# baseboard.net
KiCad netlist of a schematic drawn in Altium Designer
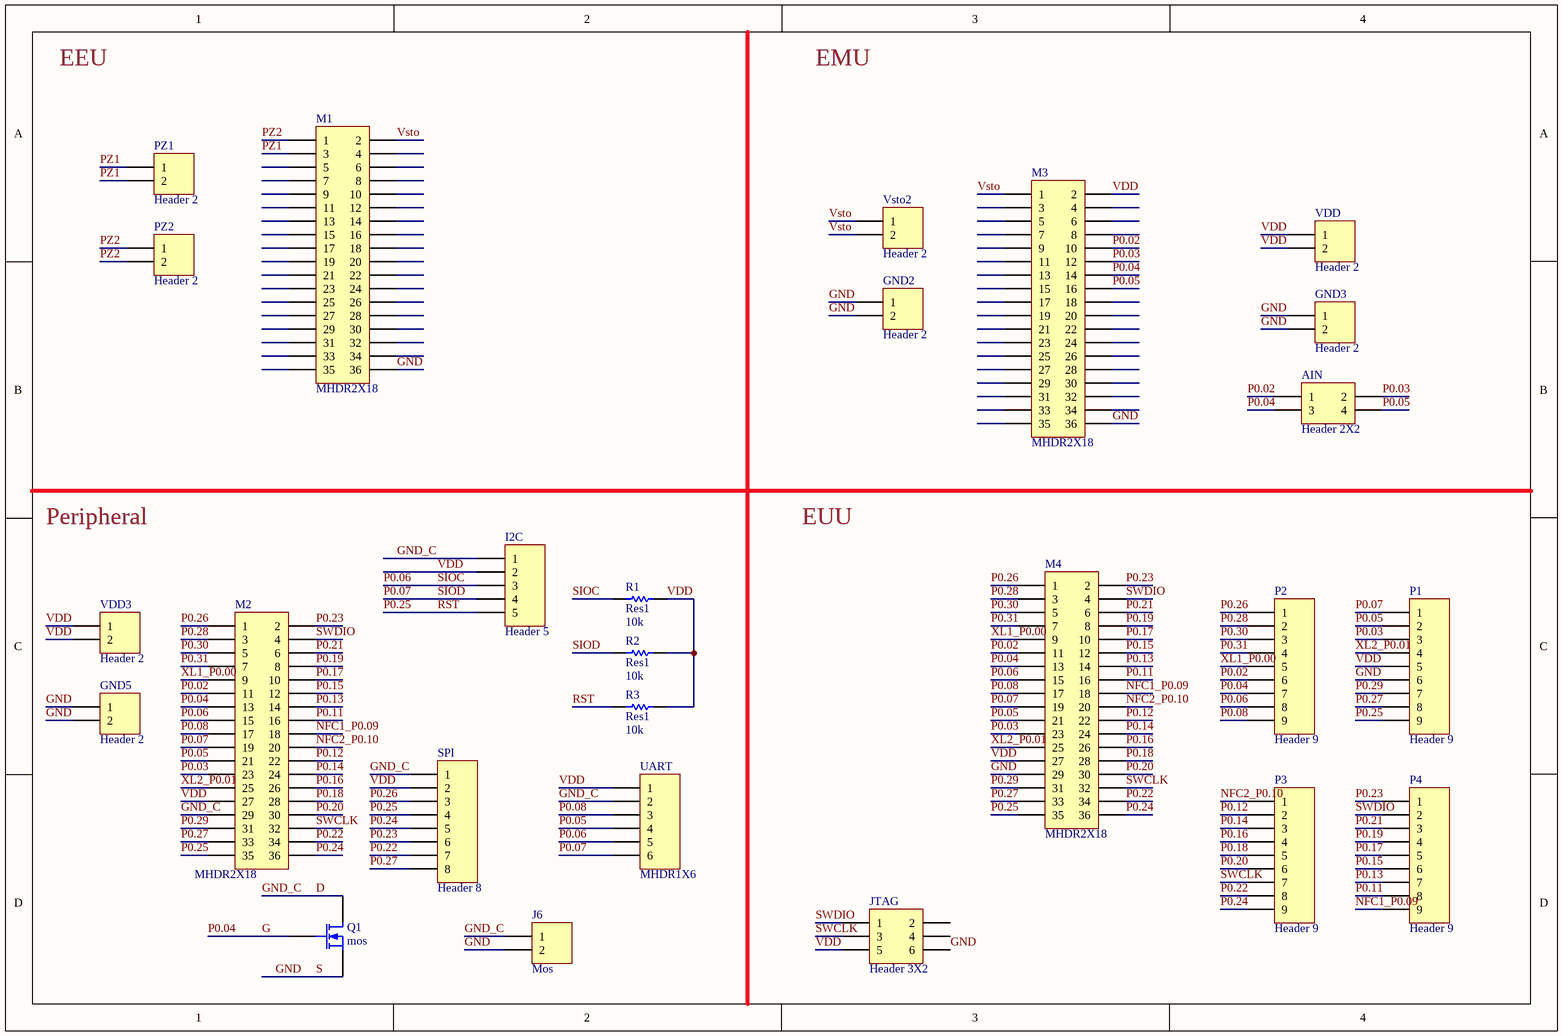
[diagram p0: baseboard.SchDoc]

(export (version "E")
  (design (tool "Eeschema 10.0.6"))
  (components
    (comp (ref "AIN")
      (value "Header 2X2")
      (footprint "HDR2X2")
      (description "Header, 2-Pin, Dual row")
      (fields (field (name "PUBLISHER") "Altium Limited"))
      (libsource (lib "Miscellaneous Connectors") (part "Header 2X2"))
    )
    (comp (ref "GND2")
      (value "Header 2")
      (footprint "HDR1X2")
      (description "Header, 2-Pin")
      (fields (field (name "PUBLISHER") "Altium Limited"))
      (libsource (lib "Miscellaneous Connectors") (part "Header 2"))
    )
    (comp (ref "GND3")
      (value "Header 2")
      (footprint "HDR1X2")
      (description "Header, 2-Pin")
      (fields (field (name "PUBLISHER") "Altium Limited"))
      (libsource (lib "Miscellaneous Connectors") (part "Header 2"))
    )
    (comp (ref "GND5")
      (value "Header 2")
      (footprint "HDR1X2")
      (description "Header, 2-Pin")
      (fields (field (name "PUBLISHER") "Altium Limited"))
      (libsource (lib "Miscellaneous Connectors") (part "Header 2"))
    )
    (comp (ref "I2C")
      (value "Header 5")
      (footprint "HDR1X5")
      (description "Header, 5-Pin")
      (fields (field (name "PUBLISHER") "Altium Limited"))
      (libsource (lib "Miscellaneous Connectors") (part "Header 5"))
    )
    (comp (ref "J6")
      (value "Mos")
      (footprint "HDR1X2")
      (description "Header, 2-Pin")
      (fields (field (name "PUBLISHER") "Altium Limited"))
      (libsource (lib "Miscellaneous Connectors") (part "Header 2"))
    )
    (comp (ref "JTAG")
      (value "Header 3X2")
      (footprint "HDR2X3")
      (description "Header, 3-Pin, Dual row")
      (fields (field (name "PUBLISHER") "Altium Limited"))
      (libsource (lib "Miscellaneous Connectors") (part "Header 3X2"))
    )
    (comp (ref "M1")
      (value "MHDR2X18")
      (footprint "module9x4")
      (description "Header, 18-Pin, Dual row")
      (fields (field (name "PUBLISHER") "Altium Limited"))
      (libsource (lib "Miscellaneous Connectors") (part "MHDR2X18"))
    )
    (comp (ref "M2")
      (value "MHDR2X18")
      (footprint "module9x4")
      (description "Header, 18-Pin, Dual row")
      (fields (field (name "PUBLISHER") "Altium Limited"))
      (libsource (lib "Miscellaneous Connectors") (part "MHDR2X18"))
    )
    (comp (ref "M3")
      (value "MHDR2X18")
      (footprint "module9x4")
      (description "Header, 18-Pin, Dual row")
      (fields (field (name "PUBLISHER") "Altium Limited"))
      (libsource (lib "Miscellaneous Connectors") (part "MHDR2X18"))
    )
    (comp (ref "M4")
      (value "MHDR2X18")
      (footprint "module9x4")
      (description "Header, 18-Pin, Dual row")
      (fields (field (name "PUBLISHER") "Altium Limited"))
      (libsource (lib "Miscellaneous Connectors") (part "MHDR2X18"))
    )
    (comp (ref "P1")
      (value "Header 9")
      (footprint "HDR1X9")
      (description "Header, 9-Pin")
      (fields (field (name "PUBLISHER") "Altium Limited"))
      (libsource (lib "Miscellaneous Connectors") (part "Header 9"))
    )
    (comp (ref "P2")
      (value "Header 9")
      (footprint "HDR1X9")
      (description "Header, 9-Pin")
      (fields (field (name "PUBLISHER") "Altium Limited"))
      (libsource (lib "Miscellaneous Connectors") (part "Header 9"))
    )
    (comp (ref "P3")
      (value "Header 9")
      (footprint "HDR1X9")
      (description "Header, 9-Pin")
      (fields (field (name "PUBLISHER") "Altium Limited"))
      (libsource (lib "Miscellaneous Connectors") (part "Header 9"))
    )
    (comp (ref "P4")
      (value "Header 9")
      (footprint "HDR1X9")
      (description "Header, 9-Pin")
      (fields (field (name "PUBLISHER") "Altium Limited"))
      (libsource (lib "Miscellaneous Connectors") (part "Header 9"))
    )
    (comp (ref "PZ1")
      (value "Header 2")
      (footprint "HDR1X2")
      (description "Header, 2-Pin")
      (fields (field (name "PUBLISHER") "Altium Limited"))
      (libsource (lib "Miscellaneous Connectors") (part "Header 2"))
    )
    (comp (ref "PZ2")
      (value "Header 2")
      (footprint "HDR1X2")
      (description "Header, 2-Pin")
      (fields (field (name "PUBLISHER") "Altium Limited"))
      (libsource (lib "Miscellaneous Connectors") (part "Header 2"))
    )
    (comp (ref "Q1")
      (value "mos")
      (footprint "SOT23_N")
      (description "N-Channel MOSFET")
      (fields (field (name "PUBLISHER") "Altium Limited"))
      (libsource (lib "Miscellaneous Devices") (part "MOSFET-N"))
    )
    (comp (ref "R1")
      (value "Res1")
      (footprint "res")
      (description "Resistor")
      (fields (field (name "ALTIUM_VALUE") "10k") (field (name "PUBLISHER") "Altium Limited"))
      (libsource (lib "Miscellaneous Devices") (part "Res1"))
    )
    (comp (ref "R2")
      (value "Res1")
      (footprint "res")
      (description "Resistor")
      (fields (field (name "ALTIUM_VALUE") "10k") (field (name "PUBLISHER") "Altium Limited"))
      (libsource (lib "Miscellaneous Devices") (part "Res1"))
    )
    (comp (ref "R3")
      (value "Res1")
      (footprint "res")
      (description "Resistor")
      (fields (field (name "ALTIUM_VALUE") "10k") (field (name "PUBLISHER") "Altium Limited"))
      (libsource (lib "Miscellaneous Devices") (part "Res1"))
    )
    (comp (ref "SPI")
      (value "Header 8")
      (footprint "HDR1X8")
      (description "Header, 8-Pin")
      (fields (field (name "PUBLISHER") "Altium Limited"))
      (libsource (lib "Miscellaneous Connectors") (part "Header 8"))
    )
    (comp (ref "UART")
      (value "MHDR1X6")
      (footprint "HDR1X6")
      (description "Header, 6-Pin")
      (fields (field (name "PUBLISHER") "Altium Limited"))
      (libsource (lib "Miscellaneous Connectors") (part "MHDR1X6"))
    )
    (comp (ref "VDD")
      (value "Header 2")
      (footprint "HDR1X2")
      (description "Header, 2-Pin")
      (fields (field (name "PUBLISHER") "Altium Limited"))
      (libsource (lib "Miscellaneous Connectors") (part "Header 2"))
    )
    (comp (ref "VDD3")
      (value "Header 2")
      (footprint "HDR1X2")
      (description "Header, 2-Pin")
      (fields (field (name "PUBLISHER") "Altium Limited"))
      (libsource (lib "Miscellaneous Connectors") (part "Header 2"))
    )
    (comp (ref "Vsto2")
      (value "Header 2")
      (footprint "HDR1X2")
      (description "Header, 2-Pin")
      (fields (field (name "PUBLISHER") "Altium Limited"))
      (libsource (lib "Miscellaneous Connectors") (part "Header 2"))
    )
  )
  (nets
    (net (code "1") (name "/D") (class "Default")
      (node (ref "I2C") (pin "1") (pinfunction "1_1") (pintype "passive"))
      (node (ref "J6") (pin "1") (pinfunction "1_1") (pintype "passive"))
      (node (ref "M2") (pin "29") (pinfunction "29_29") (pintype "passive"))
      (node (ref "Q1") (pin "1") (pinfunction "D_1") (pintype "passive"))
      (node (ref "SPI") (pin "1") (pinfunction "1_1") (pintype "passive"))
      (node (ref "UART") (pin "2") (pinfunction "2_2") (pintype "passive"))
    )
    (net (code "2") (name "/G") (class "Default")
      (node (ref "AIN") (pin "3") (pinfunction "3_3") (pintype "passive"))
      (node (ref "M2") (pin "13") (pinfunction "13_13") (pintype "passive"))
      (node (ref "M3") (pin "14") (pinfunction "14_14") (pintype "passive"))
      (node (ref "M4") (pin "13") (pinfunction "13_13") (pintype "passive"))
      (node (ref "P2") (pin "7") (pinfunction "7_7") (pintype "passive"))
      (node (ref "Q1") (pin "3") (pinfunction "G_3") (pintype "passive"))
    )
    (net (code "3") (name "/GND") (class "Default")
      (node (ref "GND2") (pin "1") (pinfunction "1_1") (pintype "passive"))
      (node (ref "GND2") (pin "2") (pinfunction "2_2") (pintype "passive"))
      (node (ref "GND3") (pin "1") (pinfunction "1_1") (pintype "passive"))
      (node (ref "GND3") (pin "2") (pinfunction "2_2") (pintype "passive"))
      (node (ref "GND5") (pin "1") (pinfunction "1_1") (pintype "passive"))
      (node (ref "GND5") (pin "2") (pinfunction "2_2") (pintype "passive"))
      (node (ref "J6") (pin "2") (pinfunction "2_2") (pintype "passive"))
      (node (ref "JTAG") (pin "6") (pinfunction "6_6") (pintype "passive"))
      (node (ref "M1") (pin "36") (pinfunction "36_36") (pintype "passive"))
      (node (ref "M3") (pin "36") (pinfunction "36_36") (pintype "passive"))
      (node (ref "M4") (pin "29") (pinfunction "29_29") (pintype "passive"))
      (node (ref "P1") (pin "6") (pinfunction "6_6") (pintype "passive"))
      (node (ref "Q1") (pin "2") (pinfunction "S_2") (pintype "passive"))
    )
    (net (code "4") (name "/NFC1_P0.09") (class "Default")
      (node (ref "M2") (pin "18") (pinfunction "18_18") (pintype "passive"))
      (node (ref "M4") (pin "18") (pinfunction "18_18") (pintype "passive"))
      (node (ref "P4") (pin "9") (pinfunction "9_9") (pintype "passive"))
    )
    (net (code "5") (name "/NFC2_P0.10") (class "Default")
      (node (ref "M2") (pin "20") (pinfunction "20_20") (pintype "passive"))
      (node (ref "M4") (pin "20") (pinfunction "20_20") (pintype "passive"))
      (node (ref "P3") (pin "1") (pinfunction "1_1") (pintype "passive"))
    )
    (net (code "6") (name "/P0.02") (class "Default")
      (node (ref "AIN") (pin "1") (pinfunction "1_1") (pintype "passive"))
      (node (ref "M2") (pin "11") (pinfunction "11_11") (pintype "passive"))
      (node (ref "M3") (pin "10") (pinfunction "10_10") (pintype "passive"))
      (node (ref "M4") (pin "11") (pinfunction "11_11") (pintype "passive"))
      (node (ref "P2") (pin "6") (pinfunction "6_6") (pintype "passive"))
    )
    (net (code "7") (name "/P0.03") (class "Default")
      (node (ref "AIN") (pin "2") (pinfunction "2_2") (pintype "passive"))
      (node (ref "M2") (pin "23") (pinfunction "23_23") (pintype "passive"))
      (node (ref "M3") (pin "12") (pinfunction "12_12") (pintype "passive"))
      (node (ref "M4") (pin "23") (pinfunction "23_23") (pintype "passive"))
      (node (ref "P1") (pin "3") (pinfunction "3_3") (pintype "passive"))
    )
    (net (code "8") (name "/P0.05") (class "Default")
      (node (ref "AIN") (pin "4") (pinfunction "4_4") (pintype "passive"))
      (node (ref "M2") (pin "21") (pinfunction "21_21") (pintype "passive"))
      (node (ref "M3") (pin "16") (pinfunction "16_16") (pintype "passive"))
      (node (ref "M4") (pin "21") (pinfunction "21_21") (pintype "passive"))
      (node (ref "P1") (pin "2") (pinfunction "2_2") (pintype "passive"))
      (node (ref "UART") (pin "4") (pinfunction "4_4") (pintype "passive"))
    )
    (net (code "9") (name "/P0.06") (class "Default")
      (node (ref "I2C") (pin "3") (pinfunction "3_3") (pintype "passive"))
      (node (ref "M2") (pin "15") (pinfunction "15_15") (pintype "passive"))
      (node (ref "M4") (pin "15") (pinfunction "15_15") (pintype "passive"))
      (node (ref "P2") (pin "8") (pinfunction "8_8") (pintype "passive"))
      (node (ref "R1") (pin "1") (pinfunction "1_1") (pintype "passive"))
      (node (ref "UART") (pin "5") (pinfunction "5_5") (pintype "passive"))
    )
    (net (code "10") (name "/P0.07") (class "Default")
      (node (ref "I2C") (pin "4") (pinfunction "4_4") (pintype "passive"))
      (node (ref "M2") (pin "19") (pinfunction "19_19") (pintype "passive"))
      (node (ref "M4") (pin "19") (pinfunction "19_19") (pintype "passive"))
      (node (ref "P1") (pin "1") (pinfunction "1_1") (pintype "passive"))
      (node (ref "R2") (pin "1") (pinfunction "1_1") (pintype "passive"))
      (node (ref "UART") (pin "6") (pinfunction "6_6") (pintype "passive"))
    )
    (net (code "11") (name "/P0.08") (class "Default")
      (node (ref "M2") (pin "17") (pinfunction "17_17") (pintype "passive"))
      (node (ref "M4") (pin "17") (pinfunction "17_17") (pintype "passive"))
      (node (ref "P2") (pin "9") (pinfunction "9_9") (pintype "passive"))
      (node (ref "UART") (pin "3") (pinfunction "3_3") (pintype "passive"))
    )
    (net (code "12") (name "/P0.11") (class "Default")
      (node (ref "M2") (pin "16") (pinfunction "16_16") (pintype "passive"))
      (node (ref "M4") (pin "16") (pinfunction "16_16") (pintype "passive"))
      (node (ref "P4") (pin "8") (pinfunction "8_8") (pintype "passive"))
    )
    (net (code "13") (name "/P0.12") (class "Default")
      (node (ref "M2") (pin "22") (pinfunction "22_22") (pintype "passive"))
      (node (ref "M4") (pin "22") (pinfunction "22_22") (pintype "passive"))
      (node (ref "P3") (pin "2") (pinfunction "2_2") (pintype "passive"))
    )
    (net (code "14") (name "/P0.13") (class "Default")
      (node (ref "M2") (pin "14") (pinfunction "14_14") (pintype "passive"))
      (node (ref "M4") (pin "14") (pinfunction "14_14") (pintype "passive"))
      (node (ref "P4") (pin "7") (pinfunction "7_7") (pintype "passive"))
    )
    (net (code "15") (name "/P0.14") (class "Default")
      (node (ref "M2") (pin "24") (pinfunction "24_24") (pintype "passive"))
      (node (ref "M4") (pin "24") (pinfunction "24_24") (pintype "passive"))
      (node (ref "P3") (pin "3") (pinfunction "3_3") (pintype "passive"))
    )
    (net (code "16") (name "/P0.15") (class "Default")
      (node (ref "M2") (pin "12") (pinfunction "12_12") (pintype "passive"))
      (node (ref "M4") (pin "12") (pinfunction "12_12") (pintype "passive"))
      (node (ref "P4") (pin "6") (pinfunction "6_6") (pintype "passive"))
    )
    (net (code "17") (name "/P0.16") (class "Default")
      (node (ref "M2") (pin "26") (pinfunction "26_26") (pintype "passive"))
      (node (ref "M4") (pin "26") (pinfunction "26_26") (pintype "passive"))
      (node (ref "P3") (pin "4") (pinfunction "4_4") (pintype "passive"))
    )
    (net (code "18") (name "/P0.17") (class "Default")
      (node (ref "M2") (pin "10") (pinfunction "10_10") (pintype "passive"))
      (node (ref "M4") (pin "10") (pinfunction "10_10") (pintype "passive"))
      (node (ref "P4") (pin "5") (pinfunction "5_5") (pintype "passive"))
    )
    (net (code "19") (name "/P0.18") (class "Default")
      (node (ref "M2") (pin "28") (pinfunction "28_28") (pintype "passive"))
      (node (ref "M4") (pin "28") (pinfunction "28_28") (pintype "passive"))
      (node (ref "P3") (pin "5") (pinfunction "5_5") (pintype "passive"))
    )
    (net (code "20") (name "/P0.19") (class "Default")
      (node (ref "M2") (pin "8") (pinfunction "8_8") (pintype "passive"))
      (node (ref "M4") (pin "8") (pinfunction "8_8") (pintype "passive"))
      (node (ref "P4") (pin "4") (pinfunction "4_4") (pintype "passive"))
    )
    (net (code "21") (name "/P0.20") (class "Default")
      (node (ref "M2") (pin "30") (pinfunction "30_30") (pintype "passive"))
      (node (ref "M4") (pin "30") (pinfunction "30_30") (pintype "passive"))
      (node (ref "P3") (pin "6") (pinfunction "6_6") (pintype "passive"))
    )
    (net (code "22") (name "/P0.21") (class "Default")
      (node (ref "M2") (pin "6") (pinfunction "6_6") (pintype "passive"))
      (node (ref "M4") (pin "6") (pinfunction "6_6") (pintype "passive"))
      (node (ref "P4") (pin "3") (pinfunction "3_3") (pintype "passive"))
    )
    (net (code "23") (name "/P0.22") (class "Default")
      (node (ref "M2") (pin "34") (pinfunction "34_34") (pintype "passive"))
      (node (ref "M4") (pin "34") (pinfunction "34_34") (pintype "passive"))
      (node (ref "P3") (pin "8") (pinfunction "8_8") (pintype "passive"))
      (node (ref "SPI") (pin "7") (pinfunction "7_7") (pintype "passive"))
    )
    (net (code "24") (name "/P0.23") (class "Default")
      (node (ref "M2") (pin "2") (pinfunction "2_2") (pintype "passive"))
      (node (ref "M4") (pin "2") (pinfunction "2_2") (pintype "passive"))
      (node (ref "P4") (pin "1") (pinfunction "1_1") (pintype "passive"))
      (node (ref "SPI") (pin "6") (pinfunction "6_6") (pintype "passive"))
    )
    (net (code "25") (name "/P0.24") (class "Default")
      (node (ref "M2") (pin "36") (pinfunction "36_36") (pintype "passive"))
      (node (ref "M4") (pin "36") (pinfunction "36_36") (pintype "passive"))
      (node (ref "P3") (pin "9") (pinfunction "9_9") (pintype "passive"))
      (node (ref "SPI") (pin "5") (pinfunction "5_5") (pintype "passive"))
    )
    (net (code "26") (name "/P0.25") (class "Default")
      (node (ref "I2C") (pin "5") (pinfunction "5_5") (pintype "passive"))
      (node (ref "M2") (pin "35") (pinfunction "35_35") (pintype "passive"))
      (node (ref "M4") (pin "35") (pinfunction "35_35") (pintype "passive"))
      (node (ref "P1") (pin "9") (pinfunction "9_9") (pintype "passive"))
      (node (ref "R3") (pin "1") (pinfunction "1_1") (pintype "passive"))
      (node (ref "SPI") (pin "4") (pinfunction "4_4") (pintype "passive"))
    )
    (net (code "27") (name "/P0.26") (class "Default")
      (node (ref "M2") (pin "1") (pinfunction "1_1") (pintype "passive"))
      (node (ref "M4") (pin "1") (pinfunction "1_1") (pintype "passive"))
      (node (ref "P2") (pin "1") (pinfunction "1_1") (pintype "passive"))
      (node (ref "SPI") (pin "3") (pinfunction "3_3") (pintype "passive"))
    )
    (net (code "28") (name "/P0.27") (class "Default")
      (node (ref "M2") (pin "33") (pinfunction "33_33") (pintype "passive"))
      (node (ref "M4") (pin "33") (pinfunction "33_33") (pintype "passive"))
      (node (ref "P1") (pin "8") (pinfunction "8_8") (pintype "passive"))
      (node (ref "SPI") (pin "8") (pinfunction "8_8") (pintype "passive"))
    )
    (net (code "29") (name "/P0.28") (class "Default")
      (node (ref "M2") (pin "3") (pinfunction "3_3") (pintype "passive"))
      (node (ref "M4") (pin "3") (pinfunction "3_3") (pintype "passive"))
      (node (ref "P2") (pin "2") (pinfunction "2_2") (pintype "passive"))
    )
    (net (code "30") (name "/P0.29") (class "Default")
      (node (ref "M2") (pin "31") (pinfunction "31_31") (pintype "passive"))
      (node (ref "M4") (pin "31") (pinfunction "31_31") (pintype "passive"))
      (node (ref "P1") (pin "7") (pinfunction "7_7") (pintype "passive"))
    )
    (net (code "31") (name "/P0.30") (class "Default")
      (node (ref "M2") (pin "5") (pinfunction "5_5") (pintype "passive"))
      (node (ref "M4") (pin "5") (pinfunction "5_5") (pintype "passive"))
      (node (ref "P2") (pin "3") (pinfunction "3_3") (pintype "passive"))
    )
    (net (code "32") (name "/P0.31") (class "Default")
      (node (ref "M2") (pin "7") (pinfunction "7_7") (pintype "passive"))
      (node (ref "M4") (pin "7") (pinfunction "7_7") (pintype "passive"))
      (node (ref "P2") (pin "4") (pinfunction "4_4") (pintype "passive"))
    )
    (net (code "33") (name "/PZ1") (class "Default")
      (node (ref "M1") (pin "3") (pinfunction "3_3") (pintype "passive"))
      (node (ref "PZ1") (pin "1") (pinfunction "1_1") (pintype "passive"))
      (node (ref "PZ1") (pin "2") (pinfunction "2_2") (pintype "passive"))
    )
    (net (code "34") (name "/PZ2") (class "Default")
      (node (ref "M1") (pin "1") (pinfunction "1_1") (pintype "passive"))
      (node (ref "PZ2") (pin "1") (pinfunction "1_1") (pintype "passive"))
      (node (ref "PZ2") (pin "2") (pinfunction "2_2") (pintype "passive"))
    )
    (net (code "35") (name "/SWCLK") (class "Default")
      (node (ref "JTAG") (pin "3") (pinfunction "3_3") (pintype "passive"))
      (node (ref "M2") (pin "32") (pinfunction "32_32") (pintype "passive"))
      (node (ref "M4") (pin "32") (pinfunction "32_32") (pintype "passive"))
      (node (ref "P3") (pin "7") (pinfunction "7_7") (pintype "passive"))
    )
    (net (code "36") (name "/SWDIO") (class "Default")
      (node (ref "JTAG") (pin "1") (pinfunction "1_1") (pintype "passive"))
      (node (ref "M2") (pin "4") (pinfunction "4_4") (pintype "passive"))
      (node (ref "M4") (pin "4") (pinfunction "4_4") (pintype "passive"))
      (node (ref "P4") (pin "2") (pinfunction "2_2") (pintype "passive"))
    )
    (net (code "37") (name "/VDD") (class "Default")
      (node (ref "I2C") (pin "2") (pinfunction "2_2") (pintype "passive"))
      (node (ref "JTAG") (pin "5") (pinfunction "5_5") (pintype "passive"))
      (node (ref "M2") (pin "27") (pinfunction "27_27") (pintype "passive"))
      (node (ref "M3") (pin "2") (pinfunction "2_2") (pintype "passive"))
      (node (ref "M4") (pin "27") (pinfunction "27_27") (pintype "passive"))
      (node (ref "P1") (pin "5") (pinfunction "5_5") (pintype "passive"))
      (node (ref "R1") (pin "2") (pinfunction "2_2") (pintype "passive"))
      (node (ref "R2") (pin "2") (pinfunction "2_2") (pintype "passive"))
      (node (ref "R3") (pin "2") (pinfunction "2_2") (pintype "passive"))
      (node (ref "SPI") (pin "2") (pinfunction "2_2") (pintype "passive"))
      (node (ref "UART") (pin "1") (pinfunction "1_1") (pintype "passive"))
      (node (ref "VDD") (pin "1") (pinfunction "1_1") (pintype "passive"))
      (node (ref "VDD") (pin "2") (pinfunction "2_2") (pintype "passive"))
      (node (ref "VDD3") (pin "1") (pinfunction "1_1") (pintype "passive"))
      (node (ref "VDD3") (pin "2") (pinfunction "2_2") (pintype "passive"))
    )
    (net (code "38") (name "/Vsto") (class "Default")
      (node (ref "M1") (pin "2") (pinfunction "2_2") (pintype "passive"))
      (node (ref "M3") (pin "1") (pinfunction "1_1") (pintype "passive"))
      (node (ref "Vsto2") (pin "1") (pinfunction "1_1") (pintype "passive"))
      (node (ref "Vsto2") (pin "2") (pinfunction "2_2") (pintype "passive"))
    )
    (net (code "39") (name "/XL1_P0.00") (class "Default")
      (node (ref "M2") (pin "9") (pinfunction "9_9") (pintype "passive"))
      (node (ref "M4") (pin "9") (pinfunction "9_9") (pintype "passive"))
      (node (ref "P2") (pin "5") (pinfunction "5_5") (pintype "passive"))
    )
    (net (code "40") (name "/XL2_P0.01") (class "Default")
      (node (ref "M2") (pin "25") (pinfunction "25_25") (pintype "passive"))
      (node (ref "M4") (pin "25") (pinfunction "25_25") (pintype "passive"))
      (node (ref "P1") (pin "4") (pinfunction "4_4") (pintype "passive"))
    )
    (net (code "41") (name "unconnected-(JTAG-Pad2)") (class "Default")
      (node (ref "JTAG") (pin "2") (pinfunction "2_2") (pintype "passive"))
    )
    (net (code "42") (name "unconnected-(JTAG-Pad4)") (class "Default")
      (node (ref "JTAG") (pin "4") (pinfunction "4_4") (pintype "passive"))
    )
    (net (code "43") (name "unconnected-(M1-Pad4)") (class "Default")
      (node (ref "M1") (pin "4") (pinfunction "4_4") (pintype "passive"))
    )
    (net (code "44") (name "unconnected-(M1-Pad5)") (class "Default")
      (node (ref "M1") (pin "5") (pinfunction "5_5") (pintype "passive"))
    )
    (net (code "45") (name "unconnected-(M1-Pad6)") (class "Default")
      (node (ref "M1") (pin "6") (pinfunction "6_6") (pintype "passive"))
    )
    (net (code "46") (name "unconnected-(M1-Pad7)") (class "Default")
      (node (ref "M1") (pin "7") (pinfunction "7_7") (pintype "passive"))
    )
    (net (code "47") (name "unconnected-(M1-Pad8)") (class "Default")
      (node (ref "M1") (pin "8") (pinfunction "8_8") (pintype "passive"))
    )
    (net (code "48") (name "unconnected-(M1-Pad9)") (class "Default")
      (node (ref "M1") (pin "9") (pinfunction "9_9") (pintype "passive"))
    )
    (net (code "49") (name "unconnected-(M1-Pad10)") (class "Default")
      (node (ref "M1") (pin "10") (pinfunction "10_10") (pintype "passive"))
    )
    (net (code "50") (name "unconnected-(M1-Pad11)") (class "Default")
      (node (ref "M1") (pin "11") (pinfunction "11_11") (pintype "passive"))
    )
    (net (code "51") (name "unconnected-(M1-Pad12)") (class "Default")
      (node (ref "M1") (pin "12") (pinfunction "12_12") (pintype "passive"))
    )
    (net (code "52") (name "unconnected-(M1-Pad13)") (class "Default")
      (node (ref "M1") (pin "13") (pinfunction "13_13") (pintype "passive"))
    )
    (net (code "53") (name "unconnected-(M1-Pad14)") (class "Default")
      (node (ref "M1") (pin "14") (pinfunction "14_14") (pintype "passive"))
    )
    (net (code "54") (name "unconnected-(M1-Pad15)") (class "Default")
      (node (ref "M1") (pin "15") (pinfunction "15_15") (pintype "passive"))
    )
    (net (code "55") (name "unconnected-(M1-Pad16)") (class "Default")
      (node (ref "M1") (pin "16") (pinfunction "16_16") (pintype "passive"))
    )
    (net (code "56") (name "unconnected-(M1-Pad17)") (class "Default")
      (node (ref "M1") (pin "17") (pinfunction "17_17") (pintype "passive"))
    )
    (net (code "57") (name "unconnected-(M1-Pad18)") (class "Default")
      (node (ref "M1") (pin "18") (pinfunction "18_18") (pintype "passive"))
    )
    (net (code "58") (name "unconnected-(M1-Pad19)") (class "Default")
      (node (ref "M1") (pin "19") (pinfunction "19_19") (pintype "passive"))
    )
    (net (code "59") (name "unconnected-(M1-Pad20)") (class "Default")
      (node (ref "M1") (pin "20") (pinfunction "20_20") (pintype "passive"))
    )
    (net (code "60") (name "unconnected-(M1-Pad21)") (class "Default")
      (node (ref "M1") (pin "21") (pinfunction "21_21") (pintype "passive"))
    )
    (net (code "61") (name "unconnected-(M1-Pad22)") (class "Default")
      (node (ref "M1") (pin "22") (pinfunction "22_22") (pintype "passive"))
    )
    (net (code "62") (name "unconnected-(M1-Pad23)") (class "Default")
      (node (ref "M1") (pin "23") (pinfunction "23_23") (pintype "passive"))
    )
    (net (code "63") (name "unconnected-(M1-Pad24)") (class "Default")
      (node (ref "M1") (pin "24") (pinfunction "24_24") (pintype "passive"))
    )
    (net (code "64") (name "unconnected-(M1-Pad25)") (class "Default")
      (node (ref "M1") (pin "25") (pinfunction "25_25") (pintype "passive"))
    )
    (net (code "65") (name "unconnected-(M1-Pad26)") (class "Default")
      (node (ref "M1") (pin "26") (pinfunction "26_26") (pintype "passive"))
    )
    (net (code "66") (name "unconnected-(M1-Pad27)") (class "Default")
      (node (ref "M1") (pin "27") (pinfunction "27_27") (pintype "passive"))
    )
    (net (code "67") (name "unconnected-(M1-Pad28)") (class "Default")
      (node (ref "M1") (pin "28") (pinfunction "28_28") (pintype "passive"))
    )
    (net (code "68") (name "unconnected-(M1-Pad29)") (class "Default")
      (node (ref "M1") (pin "29") (pinfunction "29_29") (pintype "passive"))
    )
    (net (code "69") (name "unconnected-(M1-Pad30)") (class "Default")
      (node (ref "M1") (pin "30") (pinfunction "30_30") (pintype "passive"))
    )
    (net (code "70") (name "unconnected-(M1-Pad31)") (class "Default")
      (node (ref "M1") (pin "31") (pinfunction "31_31") (pintype "passive"))
    )
    (net (code "71") (name "unconnected-(M1-Pad32)") (class "Default")
      (node (ref "M1") (pin "32") (pinfunction "32_32") (pintype "passive"))
    )
    (net (code "72") (name "unconnected-(M1-Pad33)") (class "Default")
      (node (ref "M1") (pin "33") (pinfunction "33_33") (pintype "passive"))
    )
    (net (code "73") (name "unconnected-(M1-Pad34)") (class "Default")
      (node (ref "M1") (pin "34") (pinfunction "34_34") (pintype "passive"))
    )
    (net (code "74") (name "unconnected-(M1-Pad35)") (class "Default")
      (node (ref "M1") (pin "35") (pinfunction "35_35") (pintype "passive"))
    )
    (net (code "75") (name "unconnected-(M3-Pad3)") (class "Default")
      (node (ref "M3") (pin "3") (pinfunction "3_3") (pintype "passive"))
    )
    (net (code "76") (name "unconnected-(M3-Pad4)") (class "Default")
      (node (ref "M3") (pin "4") (pinfunction "4_4") (pintype "passive"))
    )
    (net (code "77") (name "unconnected-(M3-Pad5)") (class "Default")
      (node (ref "M3") (pin "5") (pinfunction "5_5") (pintype "passive"))
    )
    (net (code "78") (name "unconnected-(M3-Pad6)") (class "Default")
      (node (ref "M3") (pin "6") (pinfunction "6_6") (pintype "passive"))
    )
    (net (code "79") (name "unconnected-(M3-Pad7)") (class "Default")
      (node (ref "M3") (pin "7") (pinfunction "7_7") (pintype "passive"))
    )
    (net (code "80") (name "unconnected-(M3-Pad8)") (class "Default")
      (node (ref "M3") (pin "8") (pinfunction "8_8") (pintype "passive"))
    )
    (net (code "81") (name "unconnected-(M3-Pad9)") (class "Default")
      (node (ref "M3") (pin "9") (pinfunction "9_9") (pintype "passive"))
    )
    (net (code "82") (name "unconnected-(M3-Pad11)") (class "Default")
      (node (ref "M3") (pin "11") (pinfunction "11_11") (pintype "passive"))
    )
    (net (code "83") (name "unconnected-(M3-Pad13)") (class "Default")
      (node (ref "M3") (pin "13") (pinfunction "13_13") (pintype "passive"))
    )
    (net (code "84") (name "unconnected-(M3-Pad15)") (class "Default")
      (node (ref "M3") (pin "15") (pinfunction "15_15") (pintype "passive"))
    )
    (net (code "85") (name "unconnected-(M3-Pad17)") (class "Default")
      (node (ref "M3") (pin "17") (pinfunction "17_17") (pintype "passive"))
    )
    (net (code "86") (name "unconnected-(M3-Pad18)") (class "Default")
      (node (ref "M3") (pin "18") (pinfunction "18_18") (pintype "passive"))
    )
    (net (code "87") (name "unconnected-(M3-Pad19)") (class "Default")
      (node (ref "M3") (pin "19") (pinfunction "19_19") (pintype "passive"))
    )
    (net (code "88") (name "unconnected-(M3-Pad20)") (class "Default")
      (node (ref "M3") (pin "20") (pinfunction "20_20") (pintype "passive"))
    )
    (net (code "89") (name "unconnected-(M3-Pad21)") (class "Default")
      (node (ref "M3") (pin "21") (pinfunction "21_21") (pintype "passive"))
    )
    (net (code "90") (name "unconnected-(M3-Pad22)") (class "Default")
      (node (ref "M3") (pin "22") (pinfunction "22_22") (pintype "passive"))
    )
    (net (code "91") (name "unconnected-(M3-Pad23)") (class "Default")
      (node (ref "M3") (pin "23") (pinfunction "23_23") (pintype "passive"))
    )
    (net (code "92") (name "unconnected-(M3-Pad24)") (class "Default")
      (node (ref "M3") (pin "24") (pinfunction "24_24") (pintype "passive"))
    )
    (net (code "93") (name "unconnected-(M3-Pad25)") (class "Default")
      (node (ref "M3") (pin "25") (pinfunction "25_25") (pintype "passive"))
    )
    (net (code "94") (name "unconnected-(M3-Pad26)") (class "Default")
      (node (ref "M3") (pin "26") (pinfunction "26_26") (pintype "passive"))
    )
    (net (code "95") (name "unconnected-(M3-Pad27)") (class "Default")
      (node (ref "M3") (pin "27") (pinfunction "27_27") (pintype "passive"))
    )
    (net (code "96") (name "unconnected-(M3-Pad28)") (class "Default")
      (node (ref "M3") (pin "28") (pinfunction "28_28") (pintype "passive"))
    )
    (net (code "97") (name "unconnected-(M3-Pad29)") (class "Default")
      (node (ref "M3") (pin "29") (pinfunction "29_29") (pintype "passive"))
    )
    (net (code "98") (name "unconnected-(M3-Pad30)") (class "Default")
      (node (ref "M3") (pin "30") (pinfunction "30_30") (pintype "passive"))
    )
    (net (code "99") (name "unconnected-(M3-Pad31)") (class "Default")
      (node (ref "M3") (pin "31") (pinfunction "31_31") (pintype "passive"))
    )
    (net (code "100") (name "unconnected-(M3-Pad32)") (class "Default")
      (node (ref "M3") (pin "32") (pinfunction "32_32") (pintype "passive"))
    )
    (net (code "101") (name "unconnected-(M3-Pad33)") (class "Default")
      (node (ref "M3") (pin "33") (pinfunction "33_33") (pintype "passive"))
    )
    (net (code "102") (name "unconnected-(M3-Pad34)") (class "Default")
      (node (ref "M3") (pin "34") (pinfunction "34_34") (pintype "passive"))
    )
    (net (code "103") (name "unconnected-(M3-Pad35)") (class "Default")
      (node (ref "M3") (pin "35") (pinfunction "35_35") (pintype "passive"))
    )
  )
)
